# ROL2-C1-P02.net
KiCad netlist of a schematic drawn in Altium Designer
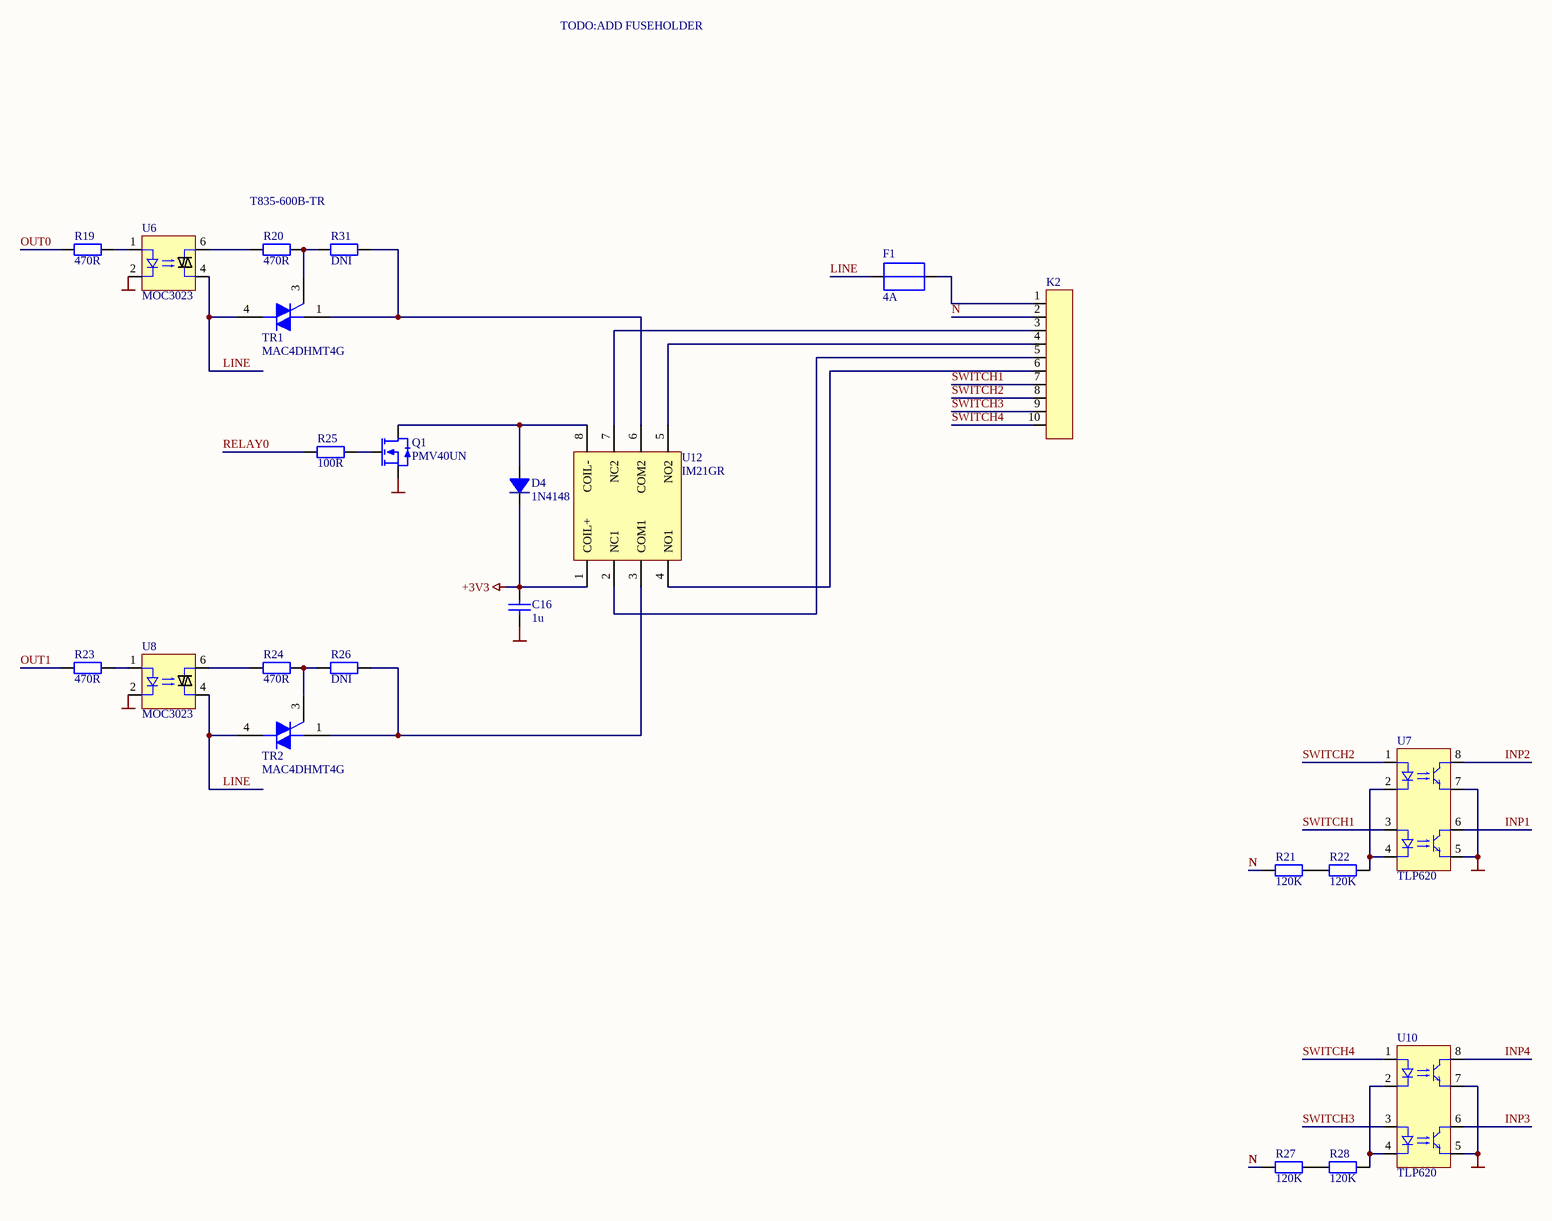
[diagram p0: ROL2-C1-P02.SchDoc]

(export (version "E")
  (design (tool "Eeschema 10.0.6"))
  (components
    (comp (ref "C16")
      (value "1u")
      (footprint "Passive:CC0805-1")
      (description "Capacitor chip ceramic 0805")
      (libsource (lib "CapChipCer") (part "CAPCC0805_1U50VX7R"))
    )
    (comp (ref "D4")
      (value "1N4148")
      (footprint "Passive:SOD-123")
      (description "Small Signal Diode")
      (fields (field (name "MANUFACTURER") "Vishay"))
      (libsource (lib "Discrete") (part "D-1N4148WS"))
    )
    (comp (ref "F1")
      (value "4A")
      (footprint "FUSE-SMD-12mm")
      (description "SMD Fuse")
      (libsource (lib "fractal_lib") (part "FUSE-4A-0464004.DR"))
    )
    (comp (ref "K2")
      (value "Terminal Block Connector, 3.81mm, Right Angle")
      (footprint "CONN_3.81_10")
      (description "Terminal Block Connector, 3.81mm, 8pin")
      (libsource (lib "fractal_lib") (part "CONN_TB_3.81_10PIN"))
    )
    (comp (ref "Q1")
      (value "PMV40UN")
      (footprint "Active:SOT23-1")
      (description "TrenchMOS ultra low level FET N-channel")
      (fields (field (name "MANUFACTURER") "NXP"))
      (libsource (lib "Discrete") (part "Q-PMV40UN"))
    )
    (comp (ref "R19")
      (value "470R")
      (footprint "RC0805-1")
      (description "Chip Resistor 0805")
      (libsource (lib "") (part "RES0805_1"))
    )
    (comp (ref "R20")
      (value "470R")
      (footprint "RC0805-1")
      (description "Chip Resistor 0805")
      (libsource (lib "") (part "RES0805_1"))
    )
    (comp (ref "R21")
      (value "120K")
      (footprint "RC1206-1")
      (description "Chip Resistor 1206")
      (libsource (lib "Resistors") (part "RES1206"))
    )
    (comp (ref "R22")
      (value "120K")
      (footprint "RC1206-1")
      (description "Chip Resistor 1206")
      (libsource (lib "Resistors") (part "RES1206"))
    )
    (comp (ref "R23")
      (value "470R")
      (footprint "RC0805-1")
      (description "Chip Resistor 0805")
      (libsource (lib "") (part "RES0805_1"))
    )
    (comp (ref "R24")
      (value "470R")
      (footprint "RC0805-1")
      (description "Chip Resistor 0805")
      (libsource (lib "Resistors") (part "RES0805"))
    )
    (comp (ref "R25")
      (value "100R")
      (footprint "RC0805-1")
      (description "Chip Resistor 0805")
      (libsource (lib "") (part "RES0805_1"))
    )
    (comp (ref "R26")
      (value "DNI")
      (footprint "RC0805-1")
      (description "Chip Resistor 0805")
      (libsource (lib "") (part "RES0805_1"))
    )
    (comp (ref "R27")
      (value "120K")
      (footprint "RC1206-1")
      (description "Chip Resistor 1206")
      (libsource (lib "Resistors") (part "RES1206"))
    )
    (comp (ref "R28")
      (value "120K")
      (footprint "RC1206-1")
      (description "Chip Resistor 1206")
      (libsource (lib "Resistors") (part "RES1206"))
    )
    (comp (ref "R31")
      (value "DNI")
      (footprint "RC0805-1")
      (description "Chip Resistor 0805")
      (libsource (lib "") (part "RES0805_1"))
    )
    (comp (ref "TR1")
      (value "MAC4DHMT4G")
      (footprint "ONSC-DPAK-3-369C-01_V")
      (description "Sensitive Gate Triacs, 3-Pin DPAK, Pb-Free, Tape and Reel")
      (fields (field (name "MANUFACTURER") "On Semiconductor"))
      (libsource (lib "fractal_lib") (part "MAC4DHMT4G"))
    )
    (comp (ref "TR2")
      (value "MAC4DHMT4G")
      (footprint "ONSC-DPAK-3-369C-01_V")
      (description "Sensitive Gate Triacs, 3-Pin DPAK, Pb-Free, Tape and Reel")
      (fields (field (name "MANUFACTURER") "On Semiconductor"))
      (libsource (lib "fractal_lib") (part "MAC4DHMT4G"))
    )
    (comp (ref "U6")
      (value "MOC3023")
      (footprint "DIP6")
      (description "digital temperature sensor")
      (libsource (lib "fractal_lib") (part "MOC3023"))
    )
    (comp (ref "U7")
      (value "TLP620")
      (footprint "DIP8")
      (description "digital temperature sensor")
      (libsource (lib "fractal_lib") (part "TLP620"))
    )
    (comp (ref "U8")
      (value "MOC3023")
      (footprint "DIP6")
      (description "digital temperature sensor")
      (libsource (lib "fractal_lib") (part "MOC3023"))
    )
    (comp (ref "U10")
      (value "TLP620")
      (footprint "DIP8")
      (description "digital temperature sensor")
      (libsource (lib "fractal_lib") (part "TLP620"))
    )
    (comp (ref "U12")
      (value "IM21GR")
      (footprint "RELAY-SMD-2A")
      (description "relay SMD 250VAC 2A")
      (libsource (lib "fractal_lib") (part "relay-SMD-IM21GR"))
    )
  )
  (nets
    (net (code "1") (name "+3V3") (class "Default")
      (node (ref "C16") (pin "2") (pinfunction "2_2") (pintype "passive"))
      (node (ref "D4") (pin "1") (pinfunction "C_1") (pintype "passive"))
      (node (ref "U12") (pin "1") (pinfunction "COIL+_1") (pintype "tri_state"))
    )
    (net (code "2") (name "/INP1") (class "Default")
      (node (ref "U7") (pin "6") (pinfunction "C_6") (pintype "passive"))
    )
    (net (code "3") (name "/INP2") (class "Default")
      (node (ref "U7") (pin "8") (pinfunction "C_8") (pintype "passive"))
    )
    (net (code "4") (name "/INP3") (class "Default")
      (node (ref "U10") (pin "6") (pinfunction "C_6") (pintype "passive"))
    )
    (net (code "5") (name "/INP4") (class "Default")
      (node (ref "U10") (pin "8") (pinfunction "C_8") (pintype "passive"))
    )
    (net (code "6") (name "/LINE") (class "Default")
      (node (ref "F1") (pin "1") (pinfunction "OUT_1") (pintype "power_in"))
      (node (ref "TR1") (pin "4") (pinfunction "MT2_4") (pintype "passive"))
      (node (ref "TR2") (pin "4") (pinfunction "MT2_4") (pintype "passive"))
      (node (ref "U6") (pin "4") (pinfunction "E_4") (pintype "passive"))
      (node (ref "U8") (pin "4") (pinfunction "E_4") (pintype "passive"))
    )
    (net (code "7") (name "/N") (class "Default")
      (node (ref "K2") (pin "2") (pinfunction "K_2") (pintype "passive"))
      (node (ref "R21") (pin "1") (pinfunction "1_1") (pintype "passive"))
      (node (ref "R27") (pin "1") (pinfunction "1_1") (pintype "passive"))
    )
    (net (code "8") (name "/OUT0") (class "Default")
      (node (ref "R19") (pin "2") (pinfunction "2_2") (pintype "passive"))
    )
    (net (code "9") (name "/OUT1") (class "Default")
      (node (ref "R23") (pin "2") (pinfunction "2_2") (pintype "passive"))
    )
    (net (code "10") (name "/RELAY0") (class "Default")
      (node (ref "R25") (pin "2") (pinfunction "2_2") (pintype "passive"))
    )
    (net (code "11") (name "/SWITCH1") (class "Default")
      (node (ref "K2") (pin "7") (pinfunction "E_7") (pintype "passive"))
      (node (ref "U7") (pin "3") (pinfunction "A_3") (pintype "passive"))
    )
    (net (code "12") (name "/SWITCH2") (class "Default")
      (node (ref "K2") (pin "8") (pinfunction "C_8") (pintype "passive"))
      (node (ref "U7") (pin "1") (pinfunction "A_1") (pintype "passive"))
    )
    (net (code "13") (name "/SWITCH3") (class "Default")
      (node (ref "K2") (pin "9") (pinfunction "C_9") (pintype "passive"))
      (node (ref "U10") (pin "3") (pinfunction "A_3") (pintype "passive"))
    )
    (net (code "14") (name "/SWITCH4") (class "Default")
      (node (ref "K2") (pin "10") (pinfunction "C_10") (pintype "passive"))
      (node (ref "U10") (pin "1") (pinfunction "A_1") (pintype "passive"))
    )
    (net (code "15") (name "GND") (class "Default")
      (node (ref "C16") (pin "1") (pinfunction "1_1") (pintype "passive"))
      (node (ref "Q1") (pin "2") (pinfunction "S_2") (pintype "passive"))
      (node (ref "U10") (pin "5") (pinfunction "E_5") (pintype "passive"))
      (node (ref "U10") (pin "7") (pinfunction "E_7") (pintype "passive"))
      (node (ref "U6") (pin "2") (pinfunction "K_2") (pintype "passive"))
      (node (ref "U7") (pin "5") (pinfunction "E_5") (pintype "passive"))
      (node (ref "U7") (pin "7") (pinfunction "E_7") (pintype "passive"))
      (node (ref "U8") (pin "2") (pinfunction "K_2") (pintype "passive"))
    )
    (net (code "16") (name "Net-(D4-A)") (class "Default")
      (node (ref "D4") (pin "2") (pinfunction "A_2") (pintype "passive"))
      (node (ref "Q1") (pin "3") (pinfunction "D_3") (pintype "passive"))
      (node (ref "U12") (pin "8") (pinfunction "COIL-_8") (pintype "tri_state"))
    )
    (net (code "17") (name "Net-(F1-IN)") (class "Default")
      (node (ref "F1") (pin "2") (pinfunction "IN_2") (pintype "passive"))
      (node (ref "K2") (pin "1") (pinfunction "A_1") (pintype "passive"))
    )
    (net (code "18") (name "Net-(Q1-G)") (class "Default")
      (node (ref "Q1") (pin "1") (pinfunction "G_1") (pintype "passive"))
      (node (ref "R25") (pin "1") (pinfunction "1_1") (pintype "passive"))
    )
    (net (code "19") (name "Net-(R21-Pad2)") (class "Default")
      (node (ref "R21") (pin "2") (pinfunction "2_2") (pintype "passive"))
      (node (ref "R22") (pin "1") (pinfunction "1_1") (pintype "passive"))
    )
    (net (code "20") (name "Net-(R22-Pad2)") (class "Default")
      (node (ref "R22") (pin "2") (pinfunction "2_2") (pintype "passive"))
      (node (ref "U7") (pin "2") (pinfunction "K_2") (pintype "passive"))
      (node (ref "U7") (pin "4") (pinfunction "K_4") (pintype "passive"))
    )
    (net (code "21") (name "Net-(R27-Pad2)") (class "Default")
      (node (ref "R27") (pin "2") (pinfunction "2_2") (pintype "passive"))
      (node (ref "R28") (pin "1") (pinfunction "1_1") (pintype "passive"))
    )
    (net (code "22") (name "Net-(R28-Pad2)") (class "Default")
      (node (ref "R28") (pin "2") (pinfunction "2_2") (pintype "passive"))
      (node (ref "U10") (pin "2") (pinfunction "K_2") (pintype "passive"))
      (node (ref "U10") (pin "4") (pinfunction "K_4") (pintype "passive"))
    )
    (net (code "23") (name "Net-(TR1-G)") (class "Default")
      (node (ref "R20") (pin "1") (pinfunction "1_1") (pintype "passive"))
      (node (ref "R31") (pin "2") (pinfunction "2_2") (pintype "passive"))
      (node (ref "TR1") (pin "3") (pinfunction "G_3") (pintype "passive"))
    )
    (net (code "24") (name "Net-(TR1-MT1)") (class "Default")
      (node (ref "R31") (pin "1") (pinfunction "1_1") (pintype "passive"))
      (node (ref "TR1") (pin "1") (pinfunction "MT1_1") (pintype "passive"))
      (node (ref "U12") (pin "6") (pinfunction "COM2_6") (pintype "tri_state"))
    )
    (net (code "25") (name "Net-(TR2-G)") (class "Default")
      (node (ref "R24") (pin "1") (pinfunction "1_1") (pintype "passive"))
      (node (ref "R26") (pin "2") (pinfunction "2_2") (pintype "passive"))
      (node (ref "TR2") (pin "3") (pinfunction "G_3") (pintype "passive"))
    )
    (net (code "26") (name "Net-(TR2-MT1)") (class "Default")
      (node (ref "R26") (pin "1") (pinfunction "1_1") (pintype "passive"))
      (node (ref "TR2") (pin "1") (pinfunction "MT1_1") (pintype "passive"))
      (node (ref "U12") (pin "3") (pinfunction "COM1_3") (pintype "tri_state"))
    )
    (net (code "27") (name "Net-(U6-A)") (class "Default")
      (node (ref "R19") (pin "1") (pinfunction "1_1") (pintype "passive"))
      (node (ref "U6") (pin "1") (pinfunction "A_1") (pintype "passive"))
    )
    (net (code "28") (name "Net-(U6-C)") (class "Default")
      (node (ref "R20") (pin "2") (pinfunction "2_2") (pintype "passive"))
      (node (ref "U6") (pin "6") (pinfunction "C_6") (pintype "passive"))
    )
    (net (code "29") (name "Net-(U8-A)") (class "Default")
      (node (ref "R23") (pin "1") (pinfunction "1_1") (pintype "passive"))
      (node (ref "U8") (pin "1") (pinfunction "A_1") (pintype "passive"))
    )
    (net (code "30") (name "Net-(U8-C)") (class "Default")
      (node (ref "R24") (pin "2") (pinfunction "2_2") (pintype "passive"))
      (node (ref "U8") (pin "6") (pinfunction "C_6") (pintype "passive"))
    )
    (net (code "31") (name "Net-(U12-NC1)") (class "Default")
      (node (ref "K2") (pin "5") (pinfunction "E_5") (pintype "passive"))
      (node (ref "U12") (pin "2") (pinfunction "NC1_2") (pintype "tri_state"))
    )
    (net (code "32") (name "Net-(U12-NC2)") (class "Default")
      (node (ref "K2") (pin "3") (pinfunction "A_3") (pintype "passive"))
      (node (ref "U12") (pin "7") (pinfunction "NC2_7") (pintype "tri_state"))
    )
    (net (code "33") (name "Net-(U12-NO1)") (class "Default")
      (node (ref "K2") (pin "6") (pinfunction "C_6") (pintype "passive"))
      (node (ref "U12") (pin "4") (pinfunction "NO1_4") (pintype "tri_state"))
    )
    (net (code "34") (name "Net-(U12-NO2)") (class "Default")
      (node (ref "K2") (pin "4") (pinfunction "K_4") (pintype "passive"))
      (node (ref "U12") (pin "5") (pinfunction "NO2_5") (pintype "tri_state"))
    )
  )
)
